# powercon_board.net
KiCad netlist of a schematic drawn in EAGLE
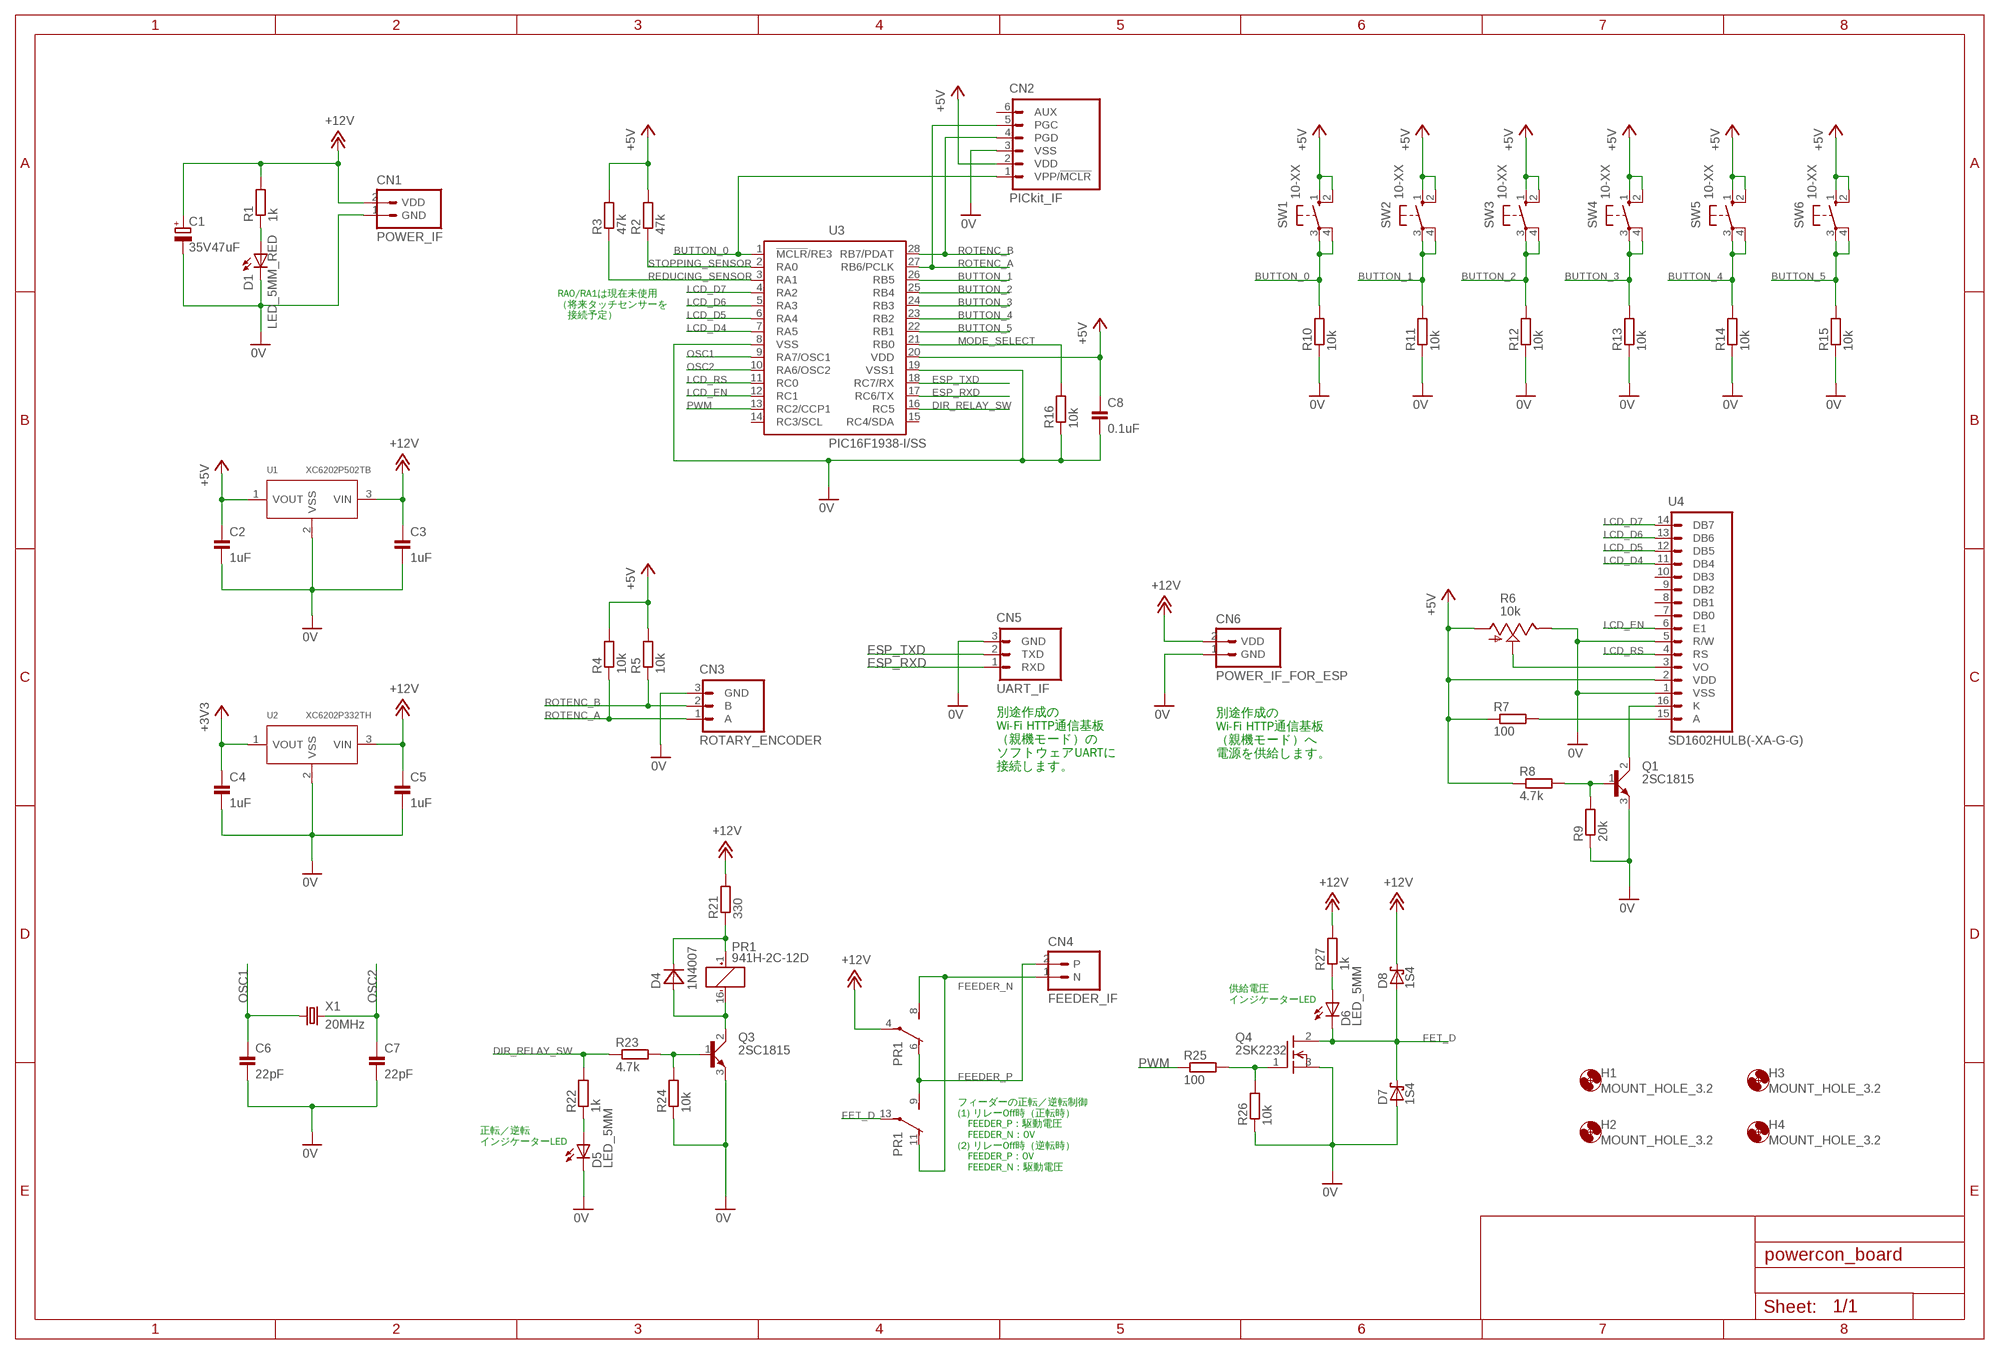
[diagram p0: schematic, sheet 1]

(export (version "E")
  (design (tool "Eeschema 10.0.6"))
  (components
    (comp (ref "C1")
      (value "35V47uF")
      (footprint "eagle-import:ELECAP_200MIL")
      (libsource (lib "eagle-import") (part "ELECAP_200MIL"))
    )
    (comp (ref "C2")
      (value "1uF")
      (footprint "eagle-import:CAP_200MIL")
      (libsource (lib "eagle-import") (part "CAP_200MIL"))
    )
    (comp (ref "C3")
      (value "1uF")
      (footprint "eagle-import:CAP_200MIL")
      (libsource (lib "eagle-import") (part "CAP_200MIL"))
    )
    (comp (ref "C4")
      (value "1uF")
      (footprint "eagle-import:CAP_200MIL")
      (libsource (lib "eagle-import") (part "CAP_200MIL"))
    )
    (comp (ref "C5")
      (value "1uF")
      (footprint "eagle-import:CAP_200MIL")
      (libsource (lib "eagle-import") (part "CAP_200MIL"))
    )
    (comp (ref "C6")
      (value "22pF")
      (footprint "eagle-import:CAP_200MIL")
      (libsource (lib "eagle-import") (part "CAP_200MIL"))
    )
    (comp (ref "C7")
      (value "22pF")
      (footprint "eagle-import:CAP_200MIL")
      (libsource (lib "eagle-import") (part "CAP_200MIL"))
    )
    (comp (ref "C8")
      (value "0.1uF")
      (footprint "eagle-import:CAP_200MIL")
      (libsource (lib "eagle-import") (part "CAP_200MIL"))
    )
    (comp (ref "CN1")
      (value "POWER_IF")
      (footprint "eagle-import:HEADER_2PIN_POWER_IF")
      (libsource (lib "eagle-import") (part "POWER_IF"))
    )
    (comp (ref "CN2")
      (value "PICkit_IF")
      (footprint "eagle-import:HEADER_6PIN")
      (libsource (lib "eagle-import") (part "PIC_CN_H"))
    )
    (comp (ref "CN3")
      (value "ROTARY_ENCODER")
      (footprint "eagle-import:HEADER_3PIN_ROT_ENC")
      (libsource (lib "eagle-import") (part "ROTARY_ENCODER"))
    )
    (comp (ref "CN4")
      (value "FEEDER_IF")
      (footprint "eagle-import:HEADER_2PIN_FEEDER_IF")
      (libsource (lib "eagle-import") (part "FEEDER_IF"))
    )
    (comp (ref "CN5")
      (value "UART_IF")
      (footprint "eagle-import:HEADER_3PIN_UART_IF")
      (libsource (lib "eagle-import") (part "UART_IF"))
    )
    (comp (ref "CN6")
      (value "POWER_IF_FOR_ESP")
      (footprint "eagle-import:HEADER_2PIN_POWER_IF")
      (libsource (lib "eagle-import") (part "POWER_IF"))
    )
    (comp (ref "D1")
      (value "LED_5MM_RED")
      (footprint "eagle-import:LED5MM")
      (libsource (lib "eagle-import") (part "LED_5MM"))
    )
    (comp (ref "D4")
      (value "1N4007")
      (footprint "eagle-import:DIODE_300MIL")
      (libsource (lib "eagle-import") (part "1N4007"))
    )
    (comp (ref "D5")
      (value "LED_5MM")
      (footprint "eagle-import:LED5MM")
      (libsource (lib "eagle-import") (part "LED_5MM"))
    )
    (comp (ref "D6")
      (value "LED_5MM")
      (footprint "eagle-import:LED5MM")
      (libsource (lib "eagle-import") (part "LED_5MM"))
    )
    (comp (ref "D7")
      (value "1S4")
      (footprint "eagle-import:DIODE-200MIL")
      (libsource (lib "eagle-import") (part "1S4"))
    )
    (comp (ref "D8")
      (value "1S4")
      (footprint "eagle-import:DIODE-200MIL")
      (libsource (lib "eagle-import") (part "1S4"))
    )
    (comp (ref "H1")
      (value "MOUNT_HOLE_3.2")
      (footprint "eagle-import:3,2")
      (libsource (lib "eagle-import") (part "MOUNT_HOLE_3.2"))
    )
    (comp (ref "H2")
      (value "MOUNT_HOLE_3.2")
      (footprint "eagle-import:3,2")
      (libsource (lib "eagle-import") (part "MOUNT_HOLE_3.2"))
    )
    (comp (ref "H3")
      (value "MOUNT_HOLE_3.2")
      (footprint "eagle-import:3,2")
      (libsource (lib "eagle-import") (part "MOUNT_HOLE_3.2"))
    )
    (comp (ref "H4")
      (value "MOUNT_HOLE_3.2")
      (footprint "eagle-import:3,2")
      (libsource (lib "eagle-import") (part "MOUNT_HOLE_3.2"))
    )
    (comp (ref "PR1")
      (value "941H-2C-12D")
      (footprint "eagle-import:941H-2C")
      (libsource (lib "eagle-import") (part "941H-2C-12D"))
    )
    (comp (ref "Q1")
      (value "2SC1815")
      (footprint "eagle-import:TO-92NL")
      (libsource (lib "eagle-import") (part "2SC1815"))
    )
    (comp (ref "Q3")
      (value "2SC1815")
      (footprint "eagle-import:TO-92NL")
      (libsource (lib "eagle-import") (part "2SC1815"))
    )
    (comp (ref "Q4")
      (value "2SK2232")
      (footprint "eagle-import:TO-220")
      (libsource (lib "eagle-import") (part "2SK2232"))
    )
    (comp (ref "R1")
      (value "1k")
      (footprint "eagle-import:RESISTOR_0207_300MIL")
      (libsource (lib "eagle-import") (part "RESISTOR_300MIL"))
    )
    (comp (ref "R2")
      (value "47k")
      (footprint "eagle-import:RESISTOR_0207_300MIL")
      (libsource (lib "eagle-import") (part "RESISTOR_300MIL"))
    )
    (comp (ref "R3")
      (value "47k")
      (footprint "eagle-import:RESISTOR_0207_300MIL")
      (libsource (lib "eagle-import") (part "RESISTOR_300MIL"))
    )
    (comp (ref "R4")
      (value "10k")
      (footprint "eagle-import:RESISTOR_0207_300MIL")
      (libsource (lib "eagle-import") (part "RESISTOR_300MIL"))
    )
    (comp (ref "R5")
      (value "10k")
      (footprint "eagle-import:RESISTOR_0207_300MIL")
      (libsource (lib "eagle-import") (part "RESISTOR_300MIL"))
    )
    (comp (ref "R6")
      (value "10k")
      (footprint "eagle-import:GF063XB")
      (libsource (lib "eagle-import") (part "GF063XB"))
    )
    (comp (ref "R7")
      (value "100")
      (footprint "eagle-import:RESISTOR_0207_300MIL")
      (libsource (lib "eagle-import") (part "RESISTOR_300MIL"))
    )
    (comp (ref "R8")
      (value "4.7k")
      (footprint "eagle-import:RESISTOR_0207_300MIL")
      (libsource (lib "eagle-import") (part "RESISTOR_300MIL"))
    )
    (comp (ref "R9")
      (value "20k")
      (footprint "eagle-import:RESISTOR_0207_300MIL")
      (libsource (lib "eagle-import") (part "RESISTOR_300MIL"))
    )
    (comp (ref "R10")
      (value "10k")
      (footprint "eagle-import:RESISTOR_0207_300MIL")
      (libsource (lib "eagle-import") (part "RESISTOR_300MIL"))
    )
    (comp (ref "R11")
      (value "10k")
      (footprint "eagle-import:RESISTOR_0207_300MIL")
      (libsource (lib "eagle-import") (part "RESISTOR_300MIL"))
    )
    (comp (ref "R12")
      (value "10k")
      (footprint "eagle-import:RESISTOR_0207_300MIL")
      (libsource (lib "eagle-import") (part "RESISTOR_300MIL"))
    )
    (comp (ref "R13")
      (value "10k")
      (footprint "eagle-import:RESISTOR_0207_300MIL")
      (libsource (lib "eagle-import") (part "RESISTOR_300MIL"))
    )
    (comp (ref "R14")
      (value "10k")
      (footprint "eagle-import:RESISTOR_0207_300MIL")
      (libsource (lib "eagle-import") (part "RESISTOR_300MIL"))
    )
    (comp (ref "R15")
      (value "10k")
      (footprint "eagle-import:RESISTOR_0207_300MIL")
      (libsource (lib "eagle-import") (part "RESISTOR_300MIL"))
    )
    (comp (ref "R16")
      (value "10k")
      (footprint "eagle-import:RESISTOR_0207_300MIL")
      (libsource (lib "eagle-import") (part "RESISTOR_300MIL"))
    )
    (comp (ref "R21")
      (value "330")
      (footprint "eagle-import:RESISTOR_0207_300MIL")
      (libsource (lib "eagle-import") (part "RESISTOR_300MIL"))
    )
    (comp (ref "R22")
      (value "1k")
      (footprint "eagle-import:RESISTOR_0207_300MIL")
      (libsource (lib "eagle-import") (part "RESISTOR_300MIL"))
    )
    (comp (ref "R23")
      (value "4.7k")
      (footprint "eagle-import:RESISTOR_0207_300MIL")
      (libsource (lib "eagle-import") (part "RESISTOR_300MIL"))
    )
    (comp (ref "R24")
      (value "10k")
      (footprint "eagle-import:RESISTOR_0207_300MIL")
      (libsource (lib "eagle-import") (part "RESISTOR_300MIL"))
    )
    (comp (ref "R25")
      (value "100")
      (footprint "eagle-import:RESISTOR_0207_300MIL")
      (libsource (lib "eagle-import") (part "RESISTOR_300MIL"))
    )
    (comp (ref "R26")
      (value "10k")
      (footprint "eagle-import:RESISTOR_0207_300MIL")
      (libsource (lib "eagle-import") (part "RESISTOR_300MIL"))
    )
    (comp (ref "R27")
      (value "1k")
      (footprint "eagle-import:RESISTOR_0207_300MIL")
      (libsource (lib "eagle-import") (part "RESISTOR_300MIL"))
    )
    (comp (ref "SW1")
      (value "10-XX")
      (footprint "eagle-import:B3F-10XX")
      (libsource (lib "eagle-import") (part "10-XX"))
    )
    (comp (ref "SW2")
      (value "10-XX")
      (footprint "eagle-import:B3F-10XX")
      (libsource (lib "eagle-import") (part "10-XX"))
    )
    (comp (ref "SW3")
      (value "10-XX")
      (footprint "eagle-import:B3F-10XX")
      (libsource (lib "eagle-import") (part "10-XX"))
    )
    (comp (ref "SW4")
      (value "10-XX")
      (footprint "eagle-import:B3F-10XX")
      (libsource (lib "eagle-import") (part "10-XX"))
    )
    (comp (ref "SW5")
      (value "10-XX")
      (footprint "eagle-import:B3F-10XX")
      (libsource (lib "eagle-import") (part "10-XX"))
    )
    (comp (ref "SW6")
      (value "10-XX")
      (footprint "eagle-import:B3F-10XX")
      (libsource (lib "eagle-import") (part "10-XX"))
    )
    (comp (ref "U1")
      (value "XC6202P502TB")
      (footprint "eagle-import:TO92-LINE")
      (libsource (lib "eagle-import") (part "XC6202P502TB"))
    )
    (comp (ref "U2")
      (value "XC6202P332TH")
      (footprint "eagle-import:TO92-LINE")
      (libsource (lib "eagle-import") (part "XC6202P332TH"))
    )
    (comp (ref "U3")
      (value "PIC16F1938-I/SS")
      (footprint "eagle-import:SSOP28")
      (libsource (lib "eagle-import") (part "PIC16F1938-I/SS"))
    )
    (comp (ref "U4")
      (value "SD1602HULB(-XA-G-G)")
      (footprint "eagle-import:HEADER_16PIN_SD1602")
      (libsource (lib "eagle-import") (part "SD1602HULB(-XA-G-G)"))
    )
    (comp (ref "X1")
      (value "20MHz")
      (footprint "eagle-import:HC-49_S")
      (libsource (lib "eagle-import") (part "HUSG-20.000-20"))
    )
  )
  (nets
    (net (code "1") (name "+3V3") (class "Default")
      (node (ref "C4") (pin "1") (pinfunction "1_1") (pintype "passive"))
      (node (ref "U2") (pin "1") (pinfunction "VOUT_1") (pintype "passive"))
    )
    (net (code "2") (name "+5V") (class "Default")
      (node (ref "C2") (pin "1") (pinfunction "1_1") (pintype "passive"))
      (node (ref "C8") (pin "1") (pinfunction "1_1") (pintype "passive"))
      (node (ref "CN2") (pin "2") (pinfunction "VDD_2") (pintype "passive"))
      (node (ref "R2") (pin "2") (pinfunction "2_2") (pintype "passive"))
      (node (ref "R3") (pin "2") (pinfunction "2_2") (pintype "passive"))
      (node (ref "R4") (pin "2") (pinfunction "2_2") (pintype "passive"))
      (node (ref "R5") (pin "2") (pinfunction "2_2") (pintype "passive"))
      (node (ref "R6") (pin "A") (pinfunction "A_A") (pintype "passive"))
      (node (ref "R7") (pin "1") (pinfunction "1_1") (pintype "passive"))
      (node (ref "R8") (pin "1") (pinfunction "1_1") (pintype "passive"))
      (node (ref "SW1") (pin "1") (pinfunction "S_1") (pintype "passive"))
      (node (ref "SW1") (pin "2") (pinfunction "S1_2") (pintype "passive"))
      (node (ref "SW2") (pin "1") (pinfunction "S_1") (pintype "passive"))
      (node (ref "SW2") (pin "2") (pinfunction "S1_2") (pintype "passive"))
      (node (ref "SW3") (pin "1") (pinfunction "S_1") (pintype "passive"))
      (node (ref "SW3") (pin "2") (pinfunction "S1_2") (pintype "passive"))
      (node (ref "SW4") (pin "1") (pinfunction "S_1") (pintype "passive"))
      (node (ref "SW4") (pin "2") (pinfunction "S1_2") (pintype "passive"))
      (node (ref "SW5") (pin "1") (pinfunction "S_1") (pintype "passive"))
      (node (ref "SW5") (pin "2") (pinfunction "S1_2") (pintype "passive"))
      (node (ref "SW6") (pin "1") (pinfunction "S_1") (pintype "passive"))
      (node (ref "SW6") (pin "2") (pinfunction "S1_2") (pintype "passive"))
      (node (ref "U1") (pin "1") (pinfunction "VOUT_1") (pintype "passive"))
      (node (ref "U3") (pin "20") (pinfunction "VDD_20") (pintype "passive"))
      (node (ref "U4") (pin "2") (pinfunction "VDD_2") (pintype "passive"))
    )
    (net (code "3") (name "+12V") (class "Default")
      (node (ref "C1") (pin "+") (pinfunction "+_+") (pintype "passive"))
      (node (ref "C3") (pin "1") (pinfunction "1_1") (pintype "passive"))
      (node (ref "C5") (pin "1") (pinfunction "1_1") (pintype "passive"))
      (node (ref "CN1") (pin "2") (pinfunction "VDD_2") (pintype "passive"))
      (node (ref "CN6") (pin "2") (pinfunction "VDD_2") (pintype "passive"))
      (node (ref "D8") (pin "C") (pinfunction "C_C") (pintype "passive"))
      (node (ref "PR1") (pin "4") (pinfunction "P_4") (pintype "passive"))
      (node (ref "R1") (pin "2") (pinfunction "2_2") (pintype "passive"))
      (node (ref "R21") (pin "2") (pinfunction "2_2") (pintype "passive"))
      (node (ref "R27") (pin "2") (pinfunction "2_2") (pintype "passive"))
      (node (ref "U1") (pin "3") (pinfunction "VIN_3") (pintype "passive"))
      (node (ref "U2") (pin "3") (pinfunction "VIN_3") (pintype "passive"))
    )
    (net (code "4") (name "/BUTTON_0") (class "Default")
      (node (ref "CN2") (pin "1") (pinfunction "VPP/~{MCLR}_1") (pintype "input"))
      (node (ref "R10") (pin "2") (pinfunction "2_2") (pintype "passive"))
      (node (ref "SW1") (pin "3") (pinfunction "P_3") (pintype "passive"))
      (node (ref "SW1") (pin "4") (pinfunction "P1_4") (pintype "passive"))
      (node (ref "U3") (pin "1") (pinfunction "~{MCLR}/RE3_1") (pintype "bidirectional"))
    )
    (net (code "5") (name "/BUTTON_1") (class "Default")
      (node (ref "R11") (pin "2") (pinfunction "2_2") (pintype "passive"))
      (node (ref "SW2") (pin "3") (pinfunction "P_3") (pintype "passive"))
      (node (ref "SW2") (pin "4") (pinfunction "P1_4") (pintype "passive"))
      (node (ref "U3") (pin "26") (pinfunction "RB5_26") (pintype "bidirectional"))
    )
    (net (code "6") (name "/BUTTON_2") (class "Default")
      (node (ref "R12") (pin "2") (pinfunction "2_2") (pintype "passive"))
      (node (ref "SW3") (pin "3") (pinfunction "P_3") (pintype "passive"))
      (node (ref "SW3") (pin "4") (pinfunction "P1_4") (pintype "passive"))
      (node (ref "U3") (pin "25") (pinfunction "RB4_25") (pintype "bidirectional"))
    )
    (net (code "7") (name "/BUTTON_3") (class "Default")
      (node (ref "R13") (pin "2") (pinfunction "2_2") (pintype "passive"))
      (node (ref "SW4") (pin "3") (pinfunction "P_3") (pintype "passive"))
      (node (ref "SW4") (pin "4") (pinfunction "P1_4") (pintype "passive"))
      (node (ref "U3") (pin "24") (pinfunction "RB3_24") (pintype "bidirectional"))
    )
    (net (code "8") (name "/BUTTON_4") (class "Default")
      (node (ref "R14") (pin "2") (pinfunction "2_2") (pintype "passive"))
      (node (ref "SW5") (pin "3") (pinfunction "P_3") (pintype "passive"))
      (node (ref "SW5") (pin "4") (pinfunction "P1_4") (pintype "passive"))
      (node (ref "U3") (pin "23") (pinfunction "RB2_23") (pintype "bidirectional"))
    )
    (net (code "9") (name "/BUTTON_5") (class "Default")
      (node (ref "R15") (pin "2") (pinfunction "2_2") (pintype "passive"))
      (node (ref "SW6") (pin "3") (pinfunction "P_3") (pintype "passive"))
      (node (ref "SW6") (pin "4") (pinfunction "P1_4") (pintype "passive"))
      (node (ref "U3") (pin "22") (pinfunction "RB1_22") (pintype "bidirectional"))
    )
    (net (code "10") (name "/DIR_RELAY_SW") (class "Default")
      (node (ref "R22") (pin "2") (pinfunction "2_2") (pintype "passive"))
      (node (ref "R23") (pin "1") (pinfunction "1_1") (pintype "passive"))
      (node (ref "U3") (pin "16") (pinfunction "RC5_16") (pintype "bidirectional"))
    )
    (net (code "11") (name "/ESP_RXD") (class "Default")
      (node (ref "CN5") (pin "1") (pinfunction "RXD_1") (pintype "bidirectional"))
      (node (ref "U3") (pin "17") (pinfunction "RC6/TX_17") (pintype "bidirectional"))
    )
    (net (code "12") (name "/ESP_TXD") (class "Default")
      (node (ref "CN5") (pin "2") (pinfunction "TXD_2") (pintype "bidirectional"))
      (node (ref "U3") (pin "18") (pinfunction "RC7/RX_18") (pintype "bidirectional"))
    )
    (net (code "13") (name "/FEEDER_N") (class "Default")
      (node (ref "CN4") (pin "1") (pinfunction "N_1") (pintype "passive"))
      (node (ref "PR1") (pin "11") (pinfunction "O_11") (pintype "passive"))
      (node (ref "PR1") (pin "8") (pinfunction "S_8") (pintype "passive"))
    )
    (net (code "14") (name "/FEEDER_P") (class "Default")
      (node (ref "CN4") (pin "2") (pinfunction "P_2") (pintype "passive"))
      (node (ref "PR1") (pin "6") (pinfunction "O_6") (pintype "passive"))
      (node (ref "PR1") (pin "9") (pinfunction "S_9") (pintype "passive"))
    )
    (net (code "15") (name "/FET_D") (class "Default")
      (node (ref "D6") (pin "K") (pinfunction "C_K") (pintype "passive"))
      (node (ref "D7") (pin "C") (pinfunction "C_C") (pintype "passive"))
      (node (ref "D8") (pin "A") (pinfunction "A_A") (pintype "passive"))
      (node (ref "PR1") (pin "13") (pinfunction "P_13") (pintype "passive"))
      (node (ref "Q4") (pin "2") (pinfunction "D_2") (pintype "passive"))
    )
    (net (code "16") (name "/LCD_D4") (class "Default")
      (node (ref "U3") (pin "7") (pinfunction "RA5_7") (pintype "bidirectional"))
      (node (ref "U4") (pin "11") (pinfunction "DB4_11") (pintype "bidirectional"))
    )
    (net (code "17") (name "/LCD_D5") (class "Default")
      (node (ref "U3") (pin "6") (pinfunction "RA4_6") (pintype "bidirectional"))
      (node (ref "U4") (pin "12") (pinfunction "DB5_12") (pintype "bidirectional"))
    )
    (net (code "18") (name "/LCD_D6") (class "Default")
      (node (ref "U3") (pin "5") (pinfunction "RA3_5") (pintype "bidirectional"))
      (node (ref "U4") (pin "13") (pinfunction "DB6_13") (pintype "bidirectional"))
    )
    (net (code "19") (name "/LCD_D7") (class "Default")
      (node (ref "U3") (pin "4") (pinfunction "RA2_4") (pintype "bidirectional"))
      (node (ref "U4") (pin "14") (pinfunction "DB7_14") (pintype "bidirectional"))
    )
    (net (code "20") (name "/LCD_EN") (class "Default")
      (node (ref "U3") (pin "12") (pinfunction "RC1_12") (pintype "bidirectional"))
      (node (ref "U4") (pin "6") (pinfunction "E1_6") (pintype "bidirectional"))
    )
    (net (code "21") (name "/LCD_RS") (class "Default")
      (node (ref "U3") (pin "11") (pinfunction "RC0_11") (pintype "bidirectional"))
      (node (ref "U4") (pin "4") (pinfunction "RS_4") (pintype "bidirectional"))
    )
    (net (code "22") (name "/MODE_SELECT") (class "Default")
      (node (ref "R16") (pin "2") (pinfunction "2_2") (pintype "passive"))
      (node (ref "U3") (pin "21") (pinfunction "RB0_21") (pintype "bidirectional"))
    )
    (net (code "23") (name "/OSC1") (class "Default")
      (node (ref "C6") (pin "1") (pinfunction "1_1") (pintype "passive"))
      (node (ref "U3") (pin "9") (pinfunction "RA7/OSC1_9") (pintype "bidirectional"))
      (node (ref "X1") (pin "1") (pinfunction "1_1") (pintype "passive"))
    )
    (net (code "24") (name "/OSC2") (class "Default")
      (node (ref "C7") (pin "1") (pinfunction "1_1") (pintype "passive"))
      (node (ref "U3") (pin "10") (pinfunction "RA6/OSC2_10") (pintype "bidirectional"))
      (node (ref "X1") (pin "2") (pinfunction "2_2") (pintype "passive"))
    )
    (net (code "25") (name "/PWM") (class "Default")
      (node (ref "R25") (pin "1") (pinfunction "1_1") (pintype "passive"))
      (node (ref "U3") (pin "13") (pinfunction "RC2/CCP1_13") (pintype "bidirectional"))
    )
    (net (code "26") (name "/REDUCING_SENSOR") (class "Default")
      (node (ref "R3") (pin "1") (pinfunction "1_1") (pintype "passive"))
      (node (ref "U3") (pin "3") (pinfunction "RA1_3") (pintype "bidirectional"))
    )
    (net (code "27") (name "/ROTENC_A") (class "Default")
      (node (ref "CN2") (pin "5") (pinfunction "PGC_5") (pintype "input"))
      (node (ref "CN3") (pin "1") (pinfunction "A_1") (pintype "bidirectional"))
      (node (ref "R4") (pin "1") (pinfunction "1_1") (pintype "passive"))
      (node (ref "U3") (pin "27") (pinfunction "RB6/PCLK_27") (pintype "bidirectional"))
    )
    (net (code "28") (name "/ROTENC_B") (class "Default")
      (node (ref "CN2") (pin "4") (pinfunction "PGD_4") (pintype "bidirectional"))
      (node (ref "CN3") (pin "2") (pinfunction "B_2") (pintype "bidirectional"))
      (node (ref "R5") (pin "1") (pinfunction "1_1") (pintype "passive"))
      (node (ref "U3") (pin "28") (pinfunction "RB7/PDAT_28") (pintype "bidirectional"))
    )
    (net (code "29") (name "/STOPPING_SENSOR") (class "Default")
      (node (ref "R2") (pin "1") (pinfunction "1_1") (pintype "passive"))
      (node (ref "U3") (pin "2") (pinfunction "RA0_2") (pintype "bidirectional"))
    )
    (net (code "30") (name "0V") (class "Default")
      (node (ref "C1") (pin "-") (pinfunction "-_-") (pintype "passive"))
      (node (ref "C2") (pin "2") (pinfunction "2_2") (pintype "passive"))
      (node (ref "C3") (pin "2") (pinfunction "2_2") (pintype "passive"))
      (node (ref "C4") (pin "2") (pinfunction "2_2") (pintype "passive"))
      (node (ref "C5") (pin "2") (pinfunction "2_2") (pintype "passive"))
      (node (ref "C6") (pin "2") (pinfunction "2_2") (pintype "passive"))
      (node (ref "C7") (pin "2") (pinfunction "2_2") (pintype "passive"))
      (node (ref "C8") (pin "2") (pinfunction "2_2") (pintype "passive"))
      (node (ref "CN1") (pin "1") (pinfunction "GND_1") (pintype "passive"))
      (node (ref "CN2") (pin "3") (pinfunction "VSS_3") (pintype "passive"))
      (node (ref "CN3") (pin "3") (pinfunction "GND_3") (pintype "passive"))
      (node (ref "CN5") (pin "3") (pinfunction "GND_3") (pintype "passive"))
      (node (ref "CN6") (pin "1") (pinfunction "GND_1") (pintype "passive"))
      (node (ref "D1") (pin "K") (pinfunction "C_K") (pintype "passive"))
      (node (ref "D5") (pin "K") (pinfunction "C_K") (pintype "passive"))
      (node (ref "D7") (pin "A") (pinfunction "A_A") (pintype "passive"))
      (node (ref "Q1") (pin "3") (pinfunction "E_3") (pintype "passive"))
      (node (ref "Q3") (pin "3") (pinfunction "E_3") (pintype "passive"))
      (node (ref "Q4") (pin "3") (pinfunction "S_3") (pintype "passive"))
      (node (ref "R10") (pin "1") (pinfunction "1_1") (pintype "passive"))
      (node (ref "R11") (pin "1") (pinfunction "1_1") (pintype "passive"))
      (node (ref "R12") (pin "1") (pinfunction "1_1") (pintype "passive"))
      (node (ref "R13") (pin "1") (pinfunction "1_1") (pintype "passive"))
      (node (ref "R14") (pin "1") (pinfunction "1_1") (pintype "passive"))
      (node (ref "R15") (pin "1") (pinfunction "1_1") (pintype "passive"))
      (node (ref "R16") (pin "1") (pinfunction "1_1") (pintype "passive"))
      (node (ref "R24") (pin "1") (pinfunction "1_1") (pintype "passive"))
      (node (ref "R26") (pin "1") (pinfunction "1_1") (pintype "passive"))
      (node (ref "R6") (pin "E") (pinfunction "E_E") (pintype "passive"))
      (node (ref "R9") (pin "1") (pinfunction "1_1") (pintype "passive"))
      (node (ref "U1") (pin "2") (pinfunction "VSS_2") (pintype "passive"))
      (node (ref "U2") (pin "2") (pinfunction "VSS_2") (pintype "passive"))
      (node (ref "U3") (pin "19") (pinfunction "VSS1_19") (pintype "passive"))
      (node (ref "U3") (pin "8") (pinfunction "VSS_8") (pintype "passive"))
      (node (ref "U4") (pin "1") (pinfunction "VSS_1") (pintype "passive"))
      (node (ref "U4") (pin "5") (pinfunction "R/W_5") (pintype "bidirectional"))
    )
    (net (code "31") (name "Net-(D1-PadA)") (class "Default")
      (node (ref "D1") (pin "A") (pinfunction "A_A") (pintype "passive"))
      (node (ref "R1") (pin "1") (pinfunction "1_1") (pintype "passive"))
    )
    (net (code "32") (name "Net-(D5-PadA)") (class "Default")
      (node (ref "D5") (pin "A") (pinfunction "A_A") (pintype "passive"))
      (node (ref "R22") (pin "1") (pinfunction "1_1") (pintype "passive"))
    )
    (net (code "33") (name "Net-(D6-PadA)") (class "Default")
      (node (ref "D6") (pin "A") (pinfunction "A_A") (pintype "passive"))
      (node (ref "R27") (pin "1") (pinfunction "1_1") (pintype "passive"))
    )
    (net (code "34") (name "Net-(PR1A-+)") (class "Default")
      (node (ref "D4") (pin "C") (pinfunction "C_C") (pintype "passive"))
      (node (ref "PR1") (pin "1") (pinfunction "+_1") (pintype "passive"))
      (node (ref "R21") (pin "1") (pinfunction "1_1") (pintype "passive"))
    )
    (net (code "35") (name "Net-(PR1A--)") (class "Default")
      (node (ref "D4") (pin "A") (pinfunction "A_A") (pintype "passive"))
      (node (ref "PR1") (pin "16") (pinfunction "-_16") (pintype "passive"))
      (node (ref "Q3") (pin "2") (pinfunction "C_2") (pintype "passive"))
    )
    (net (code "36") (name "Net-(Q1-B)") (class "Default")
      (node (ref "Q1") (pin "1") (pinfunction "B_1") (pintype "passive"))
      (node (ref "R8") (pin "2") (pinfunction "2_2") (pintype "passive"))
      (node (ref "R9") (pin "2") (pinfunction "2_2") (pintype "passive"))
    )
    (net (code "37") (name "Net-(Q1-C)") (class "Default")
      (node (ref "Q1") (pin "2") (pinfunction "C_2") (pintype "passive"))
      (node (ref "U4") (pin "16") (pinfunction "K_16") (pintype "passive"))
    )
    (net (code "38") (name "Net-(Q3-B)") (class "Default")
      (node (ref "Q3") (pin "1") (pinfunction "B_1") (pintype "passive"))
      (node (ref "R23") (pin "2") (pinfunction "2_2") (pintype "passive"))
      (node (ref "R24") (pin "2") (pinfunction "2_2") (pintype "passive"))
    )
    (net (code "39") (name "Net-(Q4-G)") (class "Default")
      (node (ref "Q4") (pin "1") (pinfunction "G_1") (pintype "passive"))
      (node (ref "R25") (pin "2") (pinfunction "2_2") (pintype "passive"))
      (node (ref "R26") (pin "2") (pinfunction "2_2") (pintype "passive"))
    )
    (net (code "40") (name "Net-(U4-A)") (class "Default")
      (node (ref "R7") (pin "2") (pinfunction "2_2") (pintype "passive"))
      (node (ref "U4") (pin "15") (pinfunction "A_15") (pintype "passive"))
    )
    (net (code "41") (name "Net-(U4-VO)") (class "Default")
      (node (ref "R6") (pin "S") (pinfunction "S_S") (pintype "passive"))
      (node (ref "U4") (pin "3") (pinfunction "VO_3") (pintype "passive"))
    )
    (net (code "42") (name "unconnected-(CN2-AUX-Pad6)") (class "Default")
      (node (ref "CN2") (pin "6") (pinfunction "AUX_6") (pintype "bidirectional"))
    )
    (net (code "43") (name "unconnected-(U3-RC3{slash}SCL-Pad14)") (class "Default")
      (node (ref "U3") (pin "14") (pinfunction "RC3/SCL_14") (pintype "bidirectional"))
    )
    (net (code "44") (name "unconnected-(U3-RC4{slash}SDA-Pad15)") (class "Default")
      (node (ref "U3") (pin "15") (pinfunction "RC4/SDA_15") (pintype "bidirectional"))
    )
    (net (code "45") (name "unconnected-(U4-DB0-Pad7)") (class "Default")
      (node (ref "U4") (pin "7") (pinfunction "DB0_7") (pintype "bidirectional"))
    )
    (net (code "46") (name "unconnected-(U4-DB1-Pad8)") (class "Default")
      (node (ref "U4") (pin "8") (pinfunction "DB1_8") (pintype "bidirectional"))
    )
    (net (code "47") (name "unconnected-(U4-DB2-Pad9)") (class "Default")
      (node (ref "U4") (pin "9") (pinfunction "DB2_9") (pintype "bidirectional"))
    )
    (net (code "48") (name "unconnected-(U4-DB3-Pad10)") (class "Default")
      (node (ref "U4") (pin "10") (pinfunction "DB3_10") (pintype "bidirectional"))
    )
  )
)
